# Mirror_TurnSignal.net
KiCad netlist of a schematic drawn in Altium Designer
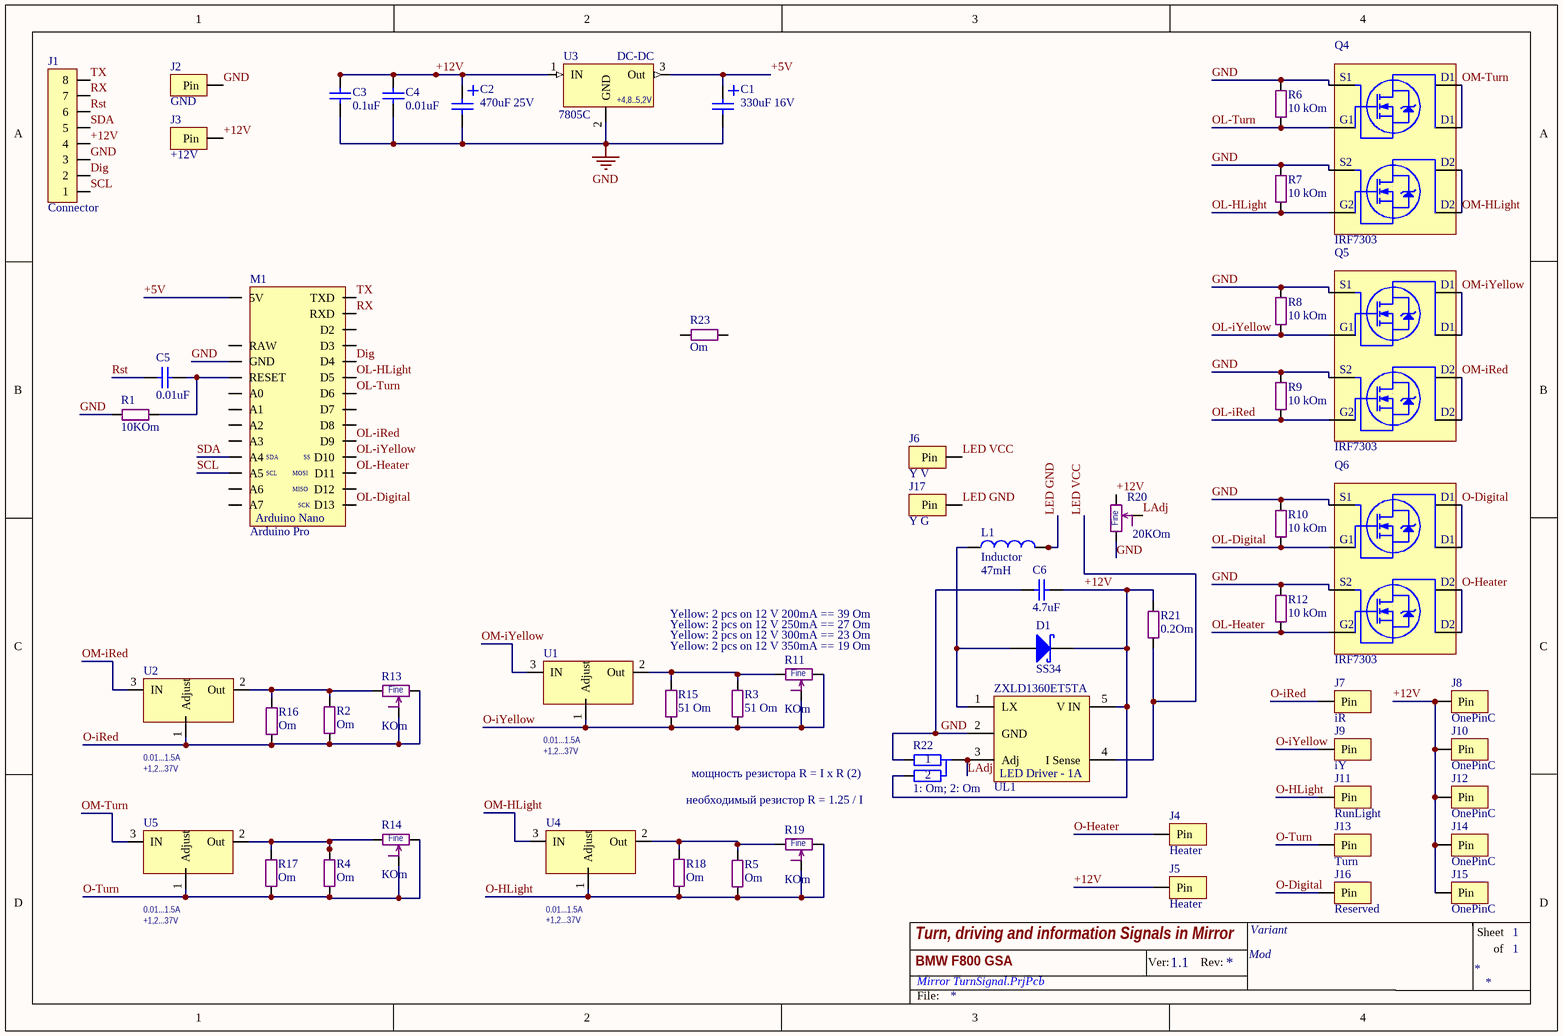
[diagram p0: Mirror TurnSignal.SchDoc]

(export (version "E")
  (design (tool "Eeschema 10.0.6"))
  (components
    (comp (ref "C1")
      (value "330uF 16V")
      (footprint "Capacitor:Cap E p3.5mm D8xH12 R - PR")
      (description "Capacitor")
      (libsource (lib "Capacitor") (part "Cap Elecrolitic"))
    )
    (comp (ref "C2")
      (value "470uF 25V")
      (footprint "Capacitor:Cap E p3.5mm D8xH12")
      (description "Capacitor")
      (libsource (lib "Capacitor") (part "Cap Elecrolitic"))
    )
    (comp (ref "C3")
      (value "0.1uF")
      (footprint "Capacitor:SMD 0805 (2012)")
      (description "Capacitor")
      (libsource (lib "Capacitor") (part "Cap SMD 0402-1812"))
    )
    (comp (ref "C4")
      (value "0.01uF")
      (footprint "Capacitor:SMD 0805 (2012)")
      (description "Capacitor")
      (libsource (lib "Capacitor") (part "Cap SMD 0402-1812"))
    )
    (comp (ref "C5")
      (value "0.01uF")
      (footprint "Capacitor:SMD 0805 (2012)")
      (description "Capacitor")
      (libsource (lib "Capacitor") (part "Cap SMD 0402-1812"))
    )
    (comp (ref "C6")
      (value "4.7uF")
      (footprint "Capacitor:SMD 1206 (3216)")
      (description "Capacitor")
      (libsource (lib "Capacitor") (part "Cap SMD 0402-1812"))
    )
    (comp (ref "D1")
      (value "SS34")
      (footprint "Diodes:DO-214AC (SMA)")
      (description "Shotki  Diode")
      (libsource (lib "Diodes") (part "D Shotki All"))
    )
    (comp (ref "J1")
      (value "Connector")
      (footprint "Connector:Molex Micro-Fit 3.0 - 8 pin D R")
      (description "Horisontal, Dbl line, Male - 3mm")
      (libsource (lib "Connector") (part "Micro-Fit 8R (2x4)"))
    )
    (comp (ref "J2")
      (value "GND")
      (footprint "Connector:OnePin 1.2x3")
      (description "Only pad")
      (libsource (lib "") (part "OnePin Connector_1"))
    )
    (comp (ref "J3")
      (value "+12V")
      (footprint "Connector:OnePin 1.2x3")
      (description "Only pad")
      (libsource (lib "") (part "OnePin Connector_1"))
    )
    (comp (ref "J4")
      (value "Heater")
      (footprint "Connector:OnePin 3x10mm Hole 0.7x8")
      (description "Only pad")
      (libsource (lib "Connector") (part "OnePin Connector"))
    )
    (comp (ref "J5")
      (value "Heater")
      (footprint "Connector:OnePin 3x10mm Hole 0.7x8")
      (description "Only pad")
      (libsource (lib "Connector") (part "OnePin Connector"))
    )
    (comp (ref "J6")
      (value "Y V")
      (footprint "Connector:OnePin 1.2x3")
      (description "Only pad")
      (libsource (lib "") (part "OnePin Connector_1"))
    )
    (comp (ref "J7")
      (value "iR")
      (footprint "Connector:OnePin 1.2x3")
      (description "Only pad")
      (libsource (lib "Connector") (part "OnePin Connector"))
    )
    (comp (ref "J8")
      (value "OnePinC")
      (footprint "Connector:OnePin 1.2x3")
      (description "Only pad")
      (libsource (lib "Connector") (part "OnePin Connector"))
    )
    (comp (ref "J9")
      (value "iY")
      (footprint "Connector:OnePin 1.2x3")
      (description "Only pad")
      (libsource (lib "Connector") (part "OnePin Connector"))
    )
    (comp (ref "J10")
      (value "OnePinC")
      (footprint "Connector:OnePin 1.2x3")
      (description "Only pad")
      (libsource (lib "Connector") (part "OnePin Connector"))
    )
    (comp (ref "J11")
      (value "RunLight")
      (footprint "Connector:OnePin 1.2x3")
      (description "Only pad")
      (libsource (lib "Connector") (part "OnePin Connector"))
    )
    (comp (ref "J12")
      (value "OnePinC")
      (footprint "Connector:OnePin 1.2x3")
      (description "Only pad")
      (libsource (lib "Connector") (part "OnePin Connector"))
    )
    (comp (ref "J13")
      (value "Turn")
      (footprint "Connector:OnePin 1.2x3")
      (description "Only pad")
      (libsource (lib "Connector") (part "OnePin Connector"))
    )
    (comp (ref "J14")
      (value "OnePinC")
      (footprint "Connector:OnePin 1.2x3")
      (description "Only pad")
      (libsource (lib "Connector") (part "OnePin Connector"))
    )
    (comp (ref "J15")
      (value "OnePinC")
      (footprint "Connector:OnePin 1.2x3")
      (description "Only pad")
      (libsource (lib "Connector") (part "OnePin Connector"))
    )
    (comp (ref "J16")
      (value "Reserved")
      (footprint "Connector:OnePin 1.2x3")
      (description "Only pad")
      (libsource (lib "Connector") (part "OnePin Connector"))
    )
    (comp (ref "J17")
      (value "Y G")
      (footprint "Connector:OnePin 1.2x3")
      (description "Only pad")
      (libsource (lib "") (part "OnePin Connector_1"))
    )
    (comp (ref "L1")
      (value "Inductor")
      (footprint "Transformers:47 mkH")
      (fields (field (name "ALTIUM_VALUE") "47mH") (field (name "PUBLISHER") "Altium Limited"))
      (libsource (lib "Transformers") (part "Inductor"))
    )
    (comp (ref "M1")
      (value "Arduino Pro")
      (footprint "Modules:Arduino Pro Mini Low (no A0-3,6-7,D3)")
      (libsource (lib "Modules") (part "Arduino Pro Micro"))
    )
    (comp (ref "Q4")
      (value "IRF7303")
      (footprint "GeneralCases:SO8")
      (description "Dual N-Ch  30V - 0.05Ω - 4.9A")
      (fields (field (name "MANUFACTURER") "Farchild"))
      (libsource (lib "Transistor") (part "IRF7303"))
    )
    (comp (ref "Q5")
      (value "IRF7303")
      (footprint "GeneralCases:SO8")
      (description "Dual N-Ch  30V - 0.05Ω - 4.9A")
      (fields (field (name "MANUFACTURER") "Farchild"))
      (libsource (lib "Transistor") (part "IRF7303"))
    )
    (comp (ref "Q6")
      (value "IRF7303")
      (footprint "GeneralCases:SO8")
      (description "Dual N-Ch  30V - 0.05Ω - 4.9A")
      (fields (field (name "MANUFACTURER") "Farchild"))
      (libsource (lib "Transistor") (part "IRF7303"))
    )
    (comp (ref "R1")
      (value "10KOm")
      (footprint "PassiveComponents:SMD 0805 (2012)")
      (libsource (lib "PassiveComponents") (part "Res All Types"))
    )
    (comp (ref "R2")
      (value "Om")
      (footprint "PassiveComponents:Res 2W p15.24")
      (libsource (lib "PassiveComponents") (part "Res All Types"))
    )
    (comp (ref "R3")
      (value "51 Om")
      (footprint "PassiveComponents:Res 2W p15.24")
      (libsource (lib "PassiveComponents") (part "Res All Types"))
    )
    (comp (ref "R4")
      (value "Om")
      (footprint "PassiveComponents:Res 2W p15.24")
      (libsource (lib "PassiveComponents") (part "Res All Types"))
    )
    (comp (ref "R5")
      (value "Om")
      (footprint "PassiveComponents:Res 2W p15.24")
      (libsource (lib "PassiveComponents") (part "Res All Types"))
    )
    (comp (ref "R6")
      (value "10 kOm")
      (footprint "PassiveComponents:SMD 0805 (2012)")
      (libsource (lib "PassiveComponents") (part "Res All Types"))
    )
    (comp (ref "R7")
      (value "10 kOm")
      (footprint "PassiveComponents:SMD 0805 (2012)")
      (libsource (lib "PassiveComponents") (part "Res All Types"))
    )
    (comp (ref "R8")
      (value "10 kOm")
      (footprint "PassiveComponents:SMD 0805 (2012)")
      (libsource (lib "PassiveComponents") (part "Res All Types"))
    )
    (comp (ref "R9")
      (value "10 kOm")
      (footprint "PassiveComponents:SMD 0805 (2012)")
      (libsource (lib "PassiveComponents") (part "Res All Types"))
    )
    (comp (ref "R10")
      (value "10 kOm")
      (footprint "PassiveComponents:SMD 0805 (2012)")
      (libsource (lib "PassiveComponents") (part "Res All Types"))
    )
    (comp (ref "R11")
      (value "КOm")
      (footprint "PassiveComponents:Res Adj 3296 Univ")
      (libsource (lib "PassiveComponents") (part "Res Adj 3296"))
    )
    (comp (ref "R12")
      (value "10 kOm")
      (footprint "PassiveComponents:SMD 0805 (2012)")
      (libsource (lib "PassiveComponents") (part "Res All Types"))
    )
    (comp (ref "R13")
      (value "КOm")
      (footprint "PassiveComponents:Res Adj 3296 Univ")
      (libsource (lib "PassiveComponents") (part "Res Adj 3296"))
    )
    (comp (ref "R14")
      (value "КOm")
      (footprint "PassiveComponents:Res Adj 3296 Univ")
      (libsource (lib "PassiveComponents") (part "Res Adj 3296"))
    )
    (comp (ref "R15")
      (value "51 Om")
      (footprint "PassiveComponents:Res 2W p15.24")
      (libsource (lib "PassiveComponents") (part "Res All Types"))
    )
    (comp (ref "R16")
      (value "Om")
      (footprint "PassiveComponents:Res 2W p15.24")
      (libsource (lib "PassiveComponents") (part "Res All Types"))
    )
    (comp (ref "R17")
      (value "Om")
      (footprint "PassiveComponents:Res 2W p15.24")
      (libsource (lib "PassiveComponents") (part "Res All Types"))
    )
    (comp (ref "R18")
      (value "Om")
      (footprint "PassiveComponents:Res 2W p15.24")
      (libsource (lib "PassiveComponents") (part "Res All Types"))
    )
    (comp (ref "R19")
      (value "КOm")
      (footprint "PassiveComponents:Res Adj 3296 Univ")
      (libsource (lib "PassiveComponents") (part "Res Adj 3296"))
    )
    (comp (ref "R20")
      (value "20КOm")
      (footprint "PassiveComponents:Res Adj 2.54 X 3")
      (libsource (lib "PassiveComponents") (part "Res Adj 3296"))
    )
    (comp (ref "R21")
      (value "0.2Om")
      (footprint "PassiveComponents:SMD 2512 (6432)")
      (libsource (lib "PassiveComponents") (part "Res All Types"))
    )
    (comp (ref "R22")
      (value "1: Om; 2: Om")
      (footprint "PassiveComponents:SMD 0805 (2012) Double")
      (description "Choice from two resistors")
      (libsource (lib "PassiveComponents") (part "Res SMD (Select one way)"))
    )
    (comp (ref "R23")
      (value "Om")
      (footprint "PassiveComponents:Res 5W L22mm, p22.86")
      (description "5W Cement")
      (libsource (lib "PassiveComponents") (part "Res 5W"))
    )
    (comp (ref "U1")
      (value "~")
      (footprint "GeneralCases:TO220 L - 20DG")
      (description "Voltage Regulator")
      (fields (field (name "I OUTPUT (A) ADJUSTABLE") "0.01...1.5A") (field (name "V OUT") "+1,2...37V"))
      (libsource (lib "PowerAdjusment") (part "LM-317"))
    )
    (comp (ref "U2")
      (value "~")
      (footprint "GeneralCases:TO220 L - 20DG")
      (description "Voltage Regulator")
      (fields (field (name "I OUTPUT (A) ADJUSTABLE") "0.01...1.5A") (field (name "V OUT") "+1,2...37V"))
      (libsource (lib "PowerAdjusment") (part "LM-317"))
    )
    (comp (ref "U3")
      (value "7805C")
      (footprint "GeneralCases:D-PAK")
      (description "Voltage Regulator")
      (fields (field (name "MANUFACTURER") "Интеграл") (field (name "V OUT") "+4,8..5,2V"))
      (libsource (lib "PowerAdjusment") (part "7805C"))
    )
    (comp (ref "U4")
      (value "~")
      (footprint "GeneralCases:TO220 L - 20DG")
      (description "Voltage Regulator")
      (fields (field (name "I OUTPUT (A) ADJUSTABLE") "0.01...1.5A") (field (name "V OUT") "+1,2...37V"))
      (libsource (lib "PowerAdjusment") (part "LM-317"))
    )
    (comp (ref "U5")
      (value "~")
      (footprint "GeneralCases:TO220 L - 20DG")
      (description "Voltage Regulator")
      (fields (field (name "I OUTPUT (A) ADJUSTABLE") "0.01...1.5A") (field (name "V OUT") "+1,2...37V"))
      (libsource (lib "PowerAdjusment") (part "LM-317"))
    )
    (comp (ref "UL1")
      (value "ZXLD1360ET5TA")
      (footprint "GeneralCases:SOT-23-5")
      (description "Led Driver - 1A, 7-30V In")
      (libsource (lib "Chips") (part "ZXLD1360ET5TA"))
    )
  )
  (nets
    (net (code "1") (name "/+5V") (class "Default")
      (node (ref "C1") (pin "1") (pinfunction "1_1") (pintype "passive"))
      (node (ref "M1") (pin "5V") (pinfunction "5V_5V") (pintype "passive"))
      (node (ref "U3") (pin "3") (pinfunction "Out_3") (pintype "output"))
    )
    (net (code "2") (name "/+12V") (class "Default")
      (node (ref "C2") (pin "1") (pinfunction "1_1") (pintype "passive"))
      (node (ref "C3") (pin "1") (pinfunction "1_1") (pintype "passive"))
      (node (ref "C4") (pin "1") (pinfunction "1_1") (pintype "passive"))
      (node (ref "C6") (pin "2") (pinfunction "2_2") (pintype "passive"))
      (node (ref "D1") (pin "K") (pinfunction "K_K") (pintype "passive"))
      (node (ref "J1") (pin "4") (pinfunction "4_4") (pintype "passive"))
      (node (ref "J10") (pin "1") (pinfunction "Pin_1") (pintype "passive"))
      (node (ref "J12") (pin "1") (pinfunction "Pin_1") (pintype "passive"))
      (node (ref "J14") (pin "1") (pinfunction "Pin_1") (pintype "passive"))
      (node (ref "J15") (pin "1") (pinfunction "Pin_1") (pintype "passive"))
      (node (ref "J3") (pin "1") (pinfunction "Pin_1") (pintype "passive"))
      (node (ref "J5") (pin "1") (pinfunction "Pin_1") (pintype "passive"))
      (node (ref "J8") (pin "1") (pinfunction "Pin_1") (pintype "passive"))
      (node (ref "R20") (pin "3") (pinfunction "3_3") (pintype "passive"))
      (node (ref "R21") (pin "2") (pinfunction "2_2") (pintype "passive"))
      (node (ref "R22") (pin "2") (pinfunction "2_2") (pintype "passive"))
      (node (ref "U3") (pin "1") (pinfunction "IN_1") (pintype "input"))
      (node (ref "UL1") (pin "5") (pinfunction "V_IN_5") (pintype "tri_state"))
    )
    (net (code "3") (name "/Dig") (class "Default")
      (node (ref "J1") (pin "2") (pinfunction "2_2") (pintype "passive"))
      (node (ref "M1") (pin "D4") (pinfunction "D4_D4") (pintype "passive"))
    )
    (net (code "4") (name "/LAdj") (class "Default")
      (node (ref "R20") (pin "2") (pinfunction "2_2") (pintype "passive"))
      (node (ref "R22") (pin "3") (pinfunction "3_3") (pintype "passive"))
      (node (ref "UL1") (pin "3") (pinfunction "Adj_3") (pintype "power_in"))
    )
    (net (code "5") (name "/LED GND") (class "Default")
      (node (ref "J17") (pin "1") (pinfunction "Pin_1") (pintype "passive"))
      (node (ref "L1") (pin "2") (pinfunction "2_2") (pintype "passive"))
    )
    (net (code "6") (name "/LED VCC") (class "Default")
      (node (ref "J6") (pin "1") (pinfunction "Pin_1") (pintype "passive"))
      (node (ref "R21") (pin "1") (pinfunction "1_1") (pintype "passive"))
      (node (ref "UL1") (pin "4") (pinfunction "I_Sense_4") (pintype "power_in"))
    )
    (net (code "7") (name "/O-Digital") (class "Default")
      (node (ref "J16") (pin "1") (pinfunction "Pin_1") (pintype "passive"))
      (node (ref "Q6") (pin "7") (pinfunction "D_7") (pintype "passive"))
      (node (ref "Q6") (pin "8") (pinfunction "D_8") (pintype "passive"))
    )
    (net (code "8") (name "/O-HLight") (class "Default")
      (node (ref "J11") (pin "1") (pinfunction "Pin_1") (pintype "passive"))
      (node (ref "R18") (pin "1") (pinfunction "1_1") (pintype "passive"))
      (node (ref "R19") (pin "2") (pinfunction "2_2") (pintype "passive"))
      (node (ref "R19") (pin "3") (pinfunction "3_3") (pintype "passive"))
      (node (ref "R5") (pin "1") (pinfunction "1_1") (pintype "passive"))
      (node (ref "U4") (pin "1") (pinfunction "Adjust_1") (pintype "passive"))
    )
    (net (code "9") (name "/O-Heater") (class "Default")
      (node (ref "J4") (pin "1") (pinfunction "Pin_1") (pintype "passive"))
      (node (ref "Q6") (pin "5") (pinfunction "D_5") (pintype "passive"))
      (node (ref "Q6") (pin "6") (pinfunction "D_6") (pintype "passive"))
    )
    (net (code "10") (name "/O-Turn") (class "Default")
      (node (ref "J13") (pin "1") (pinfunction "Pin_1") (pintype "passive"))
      (node (ref "R14") (pin "2") (pinfunction "2_2") (pintype "passive"))
      (node (ref "R14") (pin "3") (pinfunction "3_3") (pintype "passive"))
      (node (ref "R17") (pin "1") (pinfunction "1_1") (pintype "passive"))
      (node (ref "R4") (pin "1") (pinfunction "1_1") (pintype "passive"))
      (node (ref "U5") (pin "1") (pinfunction "Adjust_1") (pintype "passive"))
    )
    (net (code "11") (name "/O-iRed") (class "Default")
      (node (ref "J7") (pin "1") (pinfunction "Pin_1") (pintype "passive"))
      (node (ref "R13") (pin "2") (pinfunction "2_2") (pintype "passive"))
      (node (ref "R13") (pin "3") (pinfunction "3_3") (pintype "passive"))
      (node (ref "R16") (pin "1") (pinfunction "1_1") (pintype "passive"))
      (node (ref "R2") (pin "1") (pinfunction "1_1") (pintype "passive"))
      (node (ref "U2") (pin "1") (pinfunction "Adjust_1") (pintype "passive"))
    )
    (net (code "12") (name "/O-iYellow") (class "Default")
      (node (ref "J9") (pin "1") (pinfunction "Pin_1") (pintype "passive"))
      (node (ref "R11") (pin "2") (pinfunction "2_2") (pintype "passive"))
      (node (ref "R11") (pin "3") (pinfunction "3_3") (pintype "passive"))
      (node (ref "R15") (pin "1") (pinfunction "1_1") (pintype "passive"))
      (node (ref "R3") (pin "1") (pinfunction "1_1") (pintype "passive"))
      (node (ref "U1") (pin "1") (pinfunction "Adjust_1") (pintype "passive"))
    )
    (net (code "13") (name "/OL-Digital") (class "Default")
      (node (ref "M1") (pin "D13") (pinfunction "D13_D13") (pintype "passive"))
      (node (ref "Q6") (pin "2") (pinfunction "G_2") (pintype "passive"))
      (node (ref "R10") (pin "1") (pinfunction "1_1") (pintype "passive"))
    )
    (net (code "14") (name "/OL-HLight") (class "Default")
      (node (ref "M1") (pin "D5") (pinfunction "D5_D5") (pintype "passive"))
      (node (ref "Q4") (pin "4") (pinfunction "G_4") (pintype "passive"))
      (node (ref "R7") (pin "1") (pinfunction "1_1") (pintype "passive"))
    )
    (net (code "15") (name "/OL-Heater") (class "Default")
      (node (ref "M1") (pin "D11") (pinfunction "D11_D11") (pintype "passive"))
      (node (ref "Q6") (pin "4") (pinfunction "G_4") (pintype "passive"))
      (node (ref "R12") (pin "1") (pinfunction "1_1") (pintype "passive"))
    )
    (net (code "16") (name "/OL-Turn") (class "Default")
      (node (ref "M1") (pin "D6") (pinfunction "D6_D6") (pintype "passive"))
      (node (ref "Q4") (pin "2") (pinfunction "G_2") (pintype "passive"))
      (node (ref "R6") (pin "1") (pinfunction "1_1") (pintype "passive"))
    )
    (net (code "17") (name "/OL-iRed") (class "Default")
      (node (ref "M1") (pin "D9") (pinfunction "D9_D9") (pintype "passive"))
      (node (ref "Q5") (pin "4") (pinfunction "G_4") (pintype "passive"))
      (node (ref "R9") (pin "1") (pinfunction "1_1") (pintype "passive"))
    )
    (net (code "18") (name "/OL-iYellow") (class "Default")
      (node (ref "M1") (pin "D10") (pinfunction "D10_D10") (pintype "passive"))
      (node (ref "Q5") (pin "2") (pinfunction "G_2") (pintype "passive"))
      (node (ref "R8") (pin "1") (pinfunction "1_1") (pintype "passive"))
    )
    (net (code "19") (name "/OM-HLight") (class "Default")
      (node (ref "Q4") (pin "5") (pinfunction "D_5") (pintype "passive"))
      (node (ref "Q4") (pin "6") (pinfunction "D_6") (pintype "passive"))
      (node (ref "U4") (pin "3") (pinfunction "IN_3") (pintype "power_in"))
    )
    (net (code "20") (name "/OM-Turn") (class "Default")
      (node (ref "Q4") (pin "7") (pinfunction "D_7") (pintype "passive"))
      (node (ref "Q4") (pin "8") (pinfunction "D_8") (pintype "passive"))
      (node (ref "U5") (pin "3") (pinfunction "IN_3") (pintype "power_in"))
    )
    (net (code "21") (name "/OM-iRed") (class "Default")
      (node (ref "Q5") (pin "5") (pinfunction "D_5") (pintype "passive"))
      (node (ref "Q5") (pin "6") (pinfunction "D_6") (pintype "passive"))
      (node (ref "U2") (pin "3") (pinfunction "IN_3") (pintype "power_in"))
    )
    (net (code "22") (name "/OM-iYellow") (class "Default")
      (node (ref "Q5") (pin "7") (pinfunction "D_7") (pintype "passive"))
      (node (ref "Q5") (pin "8") (pinfunction "D_8") (pintype "passive"))
      (node (ref "U1") (pin "3") (pinfunction "IN_3") (pintype "power_in"))
    )
    (net (code "23") (name "/RX") (class "Default")
      (node (ref "J1") (pin "7") (pinfunction "7_7") (pintype "passive"))
      (node (ref "M1") (pin "RXD") (pinfunction "RXD_RXD") (pintype "passive"))
    )
    (net (code "24") (name "/Rst") (class "Default")
      (node (ref "C5") (pin "1") (pinfunction "1_1") (pintype "passive"))
      (node (ref "J1") (pin "6") (pinfunction "6_6") (pintype "passive"))
    )
    (net (code "25") (name "/SCL") (class "Default")
      (node (ref "J1") (pin "1") (pinfunction "1_1") (pintype "passive"))
      (node (ref "M1") (pin "A5") (pinfunction "A5_A5") (pintype "passive"))
    )
    (net (code "26") (name "/SDA") (class "Default")
      (node (ref "J1") (pin "5") (pinfunction "5_5") (pintype "passive"))
      (node (ref "M1") (pin "A4") (pinfunction "A4_A4") (pintype "passive"))
    )
    (net (code "27") (name "/TX") (class "Default")
      (node (ref "J1") (pin "8") (pinfunction "8_8") (pintype "passive"))
      (node (ref "M1") (pin "TXD") (pinfunction "TXD_TXD") (pintype "passive"))
    )
    (net (code "28") (name "GND") (class "Default")
      (node (ref "C1") (pin "2") (pinfunction "2_2") (pintype "passive"))
      (node (ref "C2") (pin "2") (pinfunction "2_2") (pintype "passive"))
      (node (ref "C3") (pin "2") (pinfunction "2_2") (pintype "passive"))
      (node (ref "C4") (pin "2") (pinfunction "2_2") (pintype "passive"))
      (node (ref "C6") (pin "1") (pinfunction "1_1") (pintype "passive"))
      (node (ref "J1") (pin "3") (pinfunction "3_3") (pintype "passive"))
      (node (ref "J2") (pin "1") (pinfunction "Pin_1") (pintype "passive"))
      (node (ref "M1") (pin "GND") (pinfunction "GND_GND") (pintype "passive"))
      (node (ref "Q4") (pin "1") (pinfunction "S_1") (pintype "passive"))
      (node (ref "Q4") (pin "3") (pinfunction "S_3") (pintype "passive"))
      (node (ref "Q5") (pin "1") (pinfunction "S_1") (pintype "passive"))
      (node (ref "Q5") (pin "3") (pinfunction "S_3") (pintype "passive"))
      (node (ref "Q6") (pin "1") (pinfunction "S_1") (pintype "passive"))
      (node (ref "Q6") (pin "3") (pinfunction "S_3") (pintype "passive"))
      (node (ref "R1") (pin "1") (pinfunction "1_1") (pintype "passive"))
      (node (ref "R10") (pin "2") (pinfunction "2_2") (pintype "passive"))
      (node (ref "R12") (pin "2") (pinfunction "2_2") (pintype "passive"))
      (node (ref "R20") (pin "1") (pinfunction "1_1") (pintype "passive"))
      (node (ref "R22") (pin "1") (pinfunction "1_1") (pintype "passive"))
      (node (ref "R6") (pin "2") (pinfunction "2_2") (pintype "passive"))
      (node (ref "R7") (pin "2") (pinfunction "2_2") (pintype "passive"))
      (node (ref "R8") (pin "2") (pinfunction "2_2") (pintype "passive"))
      (node (ref "R9") (pin "2") (pinfunction "2_2") (pintype "passive"))
      (node (ref "U3") (pin "2") (pinfunction "GND_2") (pintype "passive"))
      (node (ref "UL1") (pin "2") (pinfunction "GND_2") (pintype "tri_state"))
    )
    (net (code "29") (name "Net-(C5-Pad2)") (class "Default")
      (node (ref "C5") (pin "2") (pinfunction "2_2") (pintype "passive"))
      (node (ref "M1") (pin "RESET") (pinfunction "RESET_RESET") (pintype "passive"))
      (node (ref "R1") (pin "2") (pinfunction "2_2") (pintype "passive"))
    )
    (net (code "30") (name "Net-(U1-Out)") (class "Default")
      (node (ref "R11") (pin "1") (pinfunction "1_1") (pintype "passive"))
      (node (ref "R15") (pin "2") (pinfunction "2_2") (pintype "passive"))
      (node (ref "R3") (pin "2") (pinfunction "2_2") (pintype "passive"))
      (node (ref "U1") (pin "2") (pinfunction "Out_2") (pintype "power_in"))
    )
    (net (code "31") (name "Net-(U2-Out)") (class "Default")
      (node (ref "R13") (pin "1") (pinfunction "1_1") (pintype "passive"))
      (node (ref "R16") (pin "2") (pinfunction "2_2") (pintype "passive"))
      (node (ref "R2") (pin "2") (pinfunction "2_2") (pintype "passive"))
      (node (ref "U2") (pin "2") (pinfunction "Out_2") (pintype "power_in"))
    )
    (net (code "32") (name "Net-(U4-Out)") (class "Default")
      (node (ref "R18") (pin "2") (pinfunction "2_2") (pintype "passive"))
      (node (ref "R19") (pin "1") (pinfunction "1_1") (pintype "passive"))
      (node (ref "R5") (pin "2") (pinfunction "2_2") (pintype "passive"))
      (node (ref "U4") (pin "2") (pinfunction "Out_2") (pintype "power_in"))
    )
    (net (code "33") (name "Net-(U5-Out)") (class "Default")
      (node (ref "R14") (pin "1") (pinfunction "1_1") (pintype "passive"))
      (node (ref "R17") (pin "2") (pinfunction "2_2") (pintype "passive"))
      (node (ref "R4") (pin "2") (pinfunction "2_2") (pintype "passive"))
      (node (ref "U5") (pin "2") (pinfunction "Out_2") (pintype "power_in"))
    )
    (net (code "34") (name "Net-(UL1-LX)") (class "Default")
      (node (ref "D1") (pin "A") (pinfunction "A_A") (pintype "passive"))
      (node (ref "L1") (pin "1") (pinfunction "1_1") (pintype "passive"))
      (node (ref "UL1") (pin "1") (pinfunction "LX_1") (pintype "power_in"))
    )
    (net (code "35") (name "unconnected-(M1-PadA0)") (class "Default")
      (node (ref "M1") (pin "A0") (pinfunction "A0_A0") (pintype "passive"))
    )
    (net (code "36") (name "unconnected-(M1-PadA1)") (class "Default")
      (node (ref "M1") (pin "A1") (pinfunction "A1_A1") (pintype "passive"))
    )
    (net (code "37") (name "unconnected-(M1-PadA2)") (class "Default")
      (node (ref "M1") (pin "A2") (pinfunction "A2_A2") (pintype "passive"))
    )
    (net (code "38") (name "unconnected-(M1-PadA3)") (class "Default")
      (node (ref "M1") (pin "A3") (pinfunction "A3_A3") (pintype "passive"))
    )
    (net (code "39") (name "unconnected-(M1-PadA6)") (class "Default")
      (node (ref "M1") (pin "A6") (pinfunction "A6_A6") (pintype "passive"))
    )
    (net (code "40") (name "unconnected-(M1-PadA7)") (class "Default")
      (node (ref "M1") (pin "A7") (pinfunction "A7_A7") (pintype "passive"))
    )
    (net (code "41") (name "unconnected-(M1-PadD2)") (class "Default")
      (node (ref "M1") (pin "D2") (pinfunction "D2_D2") (pintype "passive"))
    )
    (net (code "42") (name "unconnected-(M1-PadD3)") (class "Default")
      (node (ref "M1") (pin "D3") (pinfunction "D3_D3") (pintype "passive"))
    )
    (net (code "43") (name "unconnected-(M1-PadD7)") (class "Default")
      (node (ref "M1") (pin "D7") (pinfunction "D7_D7") (pintype "passive"))
    )
    (net (code "44") (name "unconnected-(M1-PadD8)") (class "Default")
      (node (ref "M1") (pin "D8") (pinfunction "D8_D8") (pintype "passive"))
    )
    (net (code "45") (name "unconnected-(M1-PadD12)") (class "Default")
      (node (ref "M1") (pin "D12") (pinfunction "D12_D12") (pintype "passive"))
    )
    (net (code "46") (name "unconnected-(M1-PadRAW)") (class "Default")
      (node (ref "M1") (pin "RAW") (pinfunction "RAW_RAW") (pintype "passive"))
    )
    (net (code "47") (name "unconnected-(R23-Pad1)") (class "Default")
      (node (ref "R23") (pin "1") (pinfunction "1_1") (pintype "passive"))
    )
    (net (code "48") (name "unconnected-(R23-Pad2)") (class "Default")
      (node (ref "R23") (pin "2") (pinfunction "2_2") (pintype "passive"))
    )
  )
)
